# SKETCHES.net
KiCad netlist of a schematic drawn in EAGLE
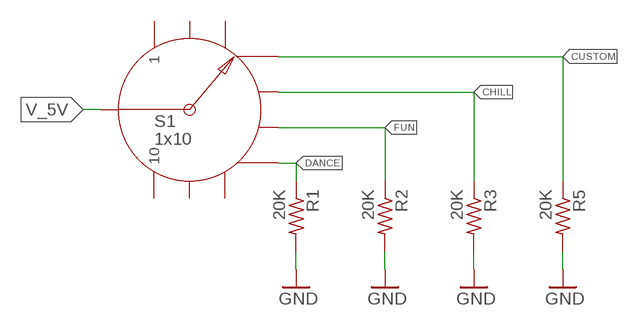
[diagram p0: schematic, sheet 1]

(export (version "E")
  (design (tool "Eeschema 10.0.6"))
  (components
    (comp (ref "R1")
      (value "20K")
      (footprint "eagle-import:R0805")
      (libsource (lib "eagle-import") (part "R-US_R0805"))
    )
    (comp (ref "R2")
      (value "20K")
      (footprint "eagle-import:R0805")
      (libsource (lib "eagle-import") (part "R-US_R0805"))
    )
    (comp (ref "R3")
      (value "20K")
      (footprint "eagle-import:R0805")
      (libsource (lib "eagle-import") (part "R-US_R0805"))
    )
    (comp (ref "R5")
      (value "20K")
      (footprint "eagle-import:R0805")
      (libsource (lib "eagle-import") (part "R-US_R0805"))
    )
    (comp (ref "S1")
      (value "1x10")
      (footprint "eagle-import:ROTARY_SWITCH_1X10")
      (libsource (lib "eagle-import") (part "SWITCH_ROTARY_1X10"))
    )
  )
  (nets
    (net (code "1") (name "CHILL") (class "Default")
      (node (ref "R3") (pin "1") (pinfunction "1_1") (pintype "passive"))
      (node (ref "S1") (pin "5") (pinfunction "5_5") (pintype "bidirectional"))
    )
    (net (code "2") (name "CUSTOM") (class "Default")
      (node (ref "R5") (pin "1") (pinfunction "1_1") (pintype "passive"))
      (node (ref "S1") (pin "4") (pinfunction "4_4") (pintype "bidirectional"))
    )
    (net (code "3") (name "DANCE") (class "Default")
      (node (ref "R1") (pin "1") (pinfunction "1_1") (pintype "passive"))
      (node (ref "S1") (pin "7") (pinfunction "7_7") (pintype "bidirectional"))
    )
    (net (code "4") (name "FUN") (class "Default")
      (node (ref "R2") (pin "1") (pinfunction "1_1") (pintype "passive"))
      (node (ref "S1") (pin "6") (pinfunction "6_6") (pintype "bidirectional"))
    )
    (net (code "5") (name "GND") (class "Default")
      (node (ref "R1") (pin "2") (pinfunction "2_2") (pintype "passive"))
      (node (ref "R2") (pin "2") (pinfunction "2_2") (pintype "passive"))
      (node (ref "R3") (pin "2") (pinfunction "2_2") (pintype "passive"))
      (node (ref "R5") (pin "2") (pinfunction "2_2") (pintype "passive"))
    )
    (net (code "6") (name "V_5V") (class "Default")
      (node (ref "S1") (pin "COMMON") (pinfunction "COMMON_COMMON") (pintype "bidirectional"))
    )
    (net (code "7") (name "unconnected-(S1-Pad1)") (class "Default")
      (node (ref "S1") (pin "1") (pinfunction "1_1") (pintype "bidirectional"))
    )
    (net (code "8") (name "unconnected-(S1-Pad2)") (class "Default")
      (node (ref "S1") (pin "2") (pinfunction "2_2") (pintype "bidirectional"))
    )
    (net (code "9") (name "unconnected-(S1-Pad3)") (class "Default")
      (node (ref "S1") (pin "3") (pinfunction "3_3") (pintype "bidirectional"))
    )
    (net (code "10") (name "unconnected-(S1-Pad8)") (class "Default")
      (node (ref "S1") (pin "8") (pinfunction "8_8") (pintype "bidirectional"))
    )
    (net (code "11") (name "unconnected-(S1-Pad9)") (class "Default")
      (node (ref "S1") (pin "9") (pinfunction "9_9") (pintype "bidirectional"))
    )
    (net (code "12") (name "unconnected-(S1-Pad10)") (class "Default")
      (node (ref "S1") (pin "10") (pinfunction "10_10") (pintype "bidirectional"))
    )
  )
)
